# FPGA_IO.net
KiCad netlist of a schematic drawn in Altium Designer
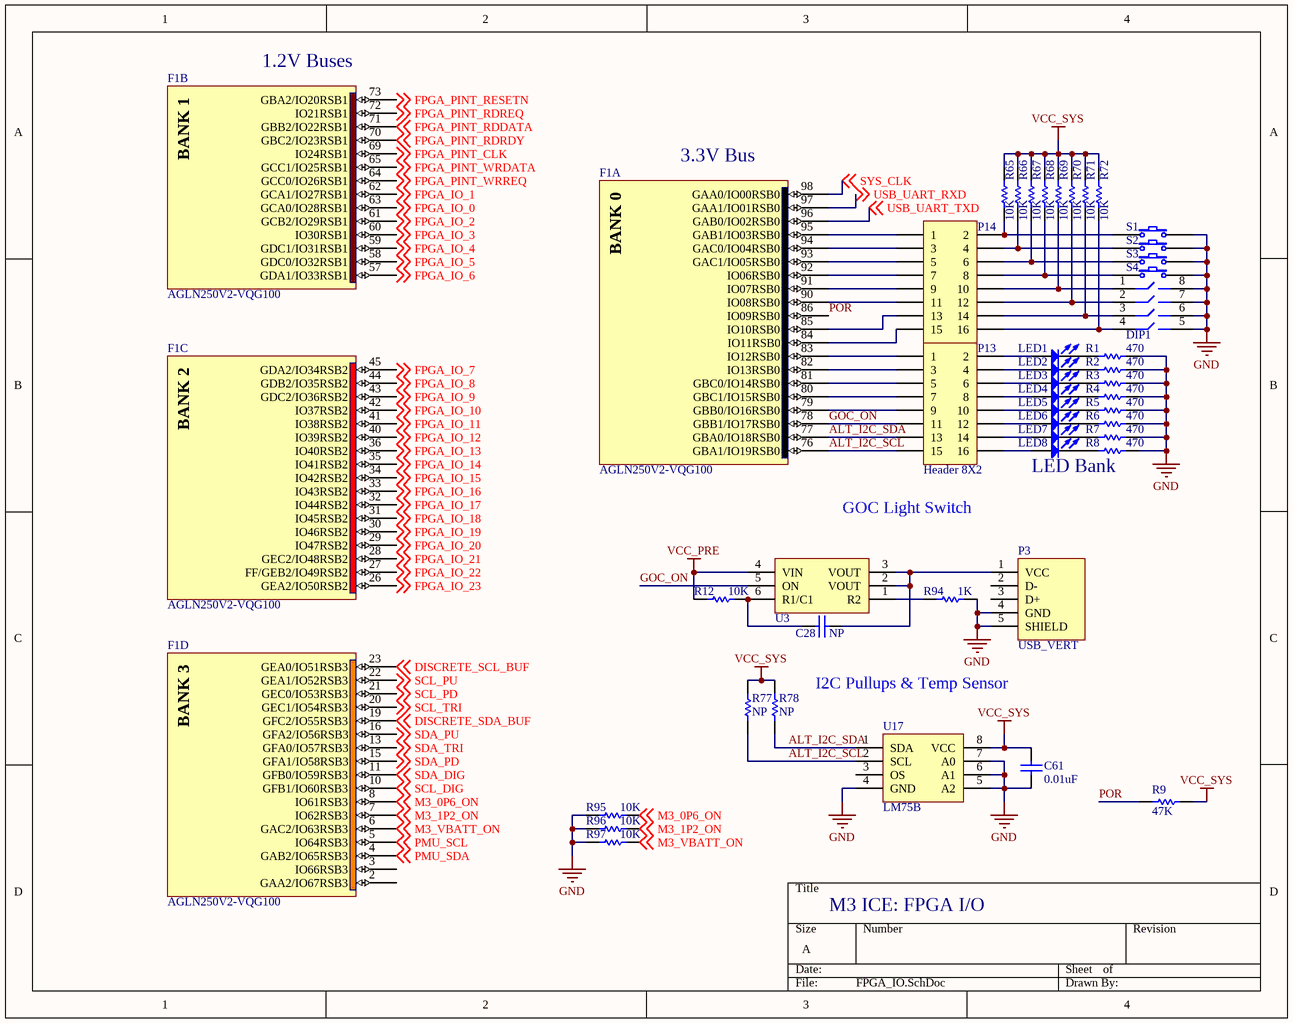
[diagram p0: FPGA_IO.SchDoc]

(export (version "E")
  (design (tool "Eeschema 10.0.6"))
  (components
    (comp (ref "C28")
      (value "NP")
      (footprint "0402")
      (description "Capacitor (Semiconductor SIM Model)")
      (fields (field (name "Comment") "Cap Semi") (field (name "PUBLISHER") "Altium Limited"))
      (libsource (lib "Miscellaneous Devices") (part "Cap Semi"))
    )
    (comp (ref "C61")
      (value "0.01uF")
      (footprint "1608[0603]")
      (description "Capacitor (Semiconductor SIM Model)")
      (fields
        (field (name "DISTPARTNO") "445-1311-1-ND")
        (field (name "MANPARTNO") "C1608X7R1H103K")
        (field (name "PUBLISHER") "Altium Limited")
      )
      (libsource (lib "Miscellaneous Devices") (part "Cap Semi"))
    )
    (comp (ref "DIP1")
      (value "ADE0404")
      (footprint "DIP-8")
      (description "4-DIP Switch")
      (fields (field (name "DISTPARTNO") "450-1364-ND"))
      (libsource (lib "M3") (part "ADE0404"))
    )
    (comp (ref "F1")
      (value "AGLN250V2-VQG100")
      (footprint "VQ100_N")
      (fields (field (name "DISTPARTNO") "1100-1134-ND") (field (name "PUBLISHER") "Altium Limited"))
      (libsource (lib "Actel IGLOO nano") (part "AGLN250V2-VQG100"))
    )
    (comp (ref "LED1")
      (value "LED 1206")
      (footprint "1206_LED")
      (fields (field (name "DISTPARTNO") "160-1169-1-ND") (field (name "MANPARTNO") "LTST-C150GKT"))
      (libsource (lib "M3") (part "LED 1206"))
    )
    (comp (ref "LED2")
      (value "LED 1206")
      (footprint "1206_LED")
      (fields (field (name "DISTPARTNO") "160-1169-1-ND") (field (name "MANPARTNO") "LTST-C150GKT"))
      (libsource (lib "M3") (part "LED 1206"))
    )
    (comp (ref "LED3")
      (value "LED 1206")
      (footprint "1206_LED")
      (fields (field (name "DISTPARTNO") "160-1169-1-ND") (field (name "MANPARTNO") "LTST-C150GKT"))
      (libsource (lib "M3") (part "LED 1206"))
    )
    (comp (ref "LED4")
      (value "LED 1206")
      (footprint "1206_LED")
      (fields (field (name "DISTPARTNO") "160-1169-1-ND") (field (name "MANPARTNO") "LTST-C150GKT"))
      (libsource (lib "M3") (part "LED 1206"))
    )
    (comp (ref "LED5")
      (value "LED 1206")
      (footprint "1206_LED")
      (fields (field (name "DISTPARTNO") "160-1169-1-ND") (field (name "MANPARTNO") "LTST-C150GKT"))
      (libsource (lib "M3") (part "LED 1206"))
    )
    (comp (ref "LED6")
      (value "LED 1206")
      (footprint "1206_LED")
      (fields (field (name "DISTPARTNO") "160-1169-1-ND") (field (name "MANPARTNO") "LTST-C150GKT"))
      (libsource (lib "M3") (part "LED 1206"))
    )
    (comp (ref "LED7")
      (value "LED 1206")
      (footprint "1206_LED")
      (fields (field (name "DISTPARTNO") "160-1169-1-ND") (field (name "MANPARTNO") "LTST-C150GKT"))
      (libsource (lib "M3") (part "LED 1206"))
    )
    (comp (ref "LED8")
      (value "LED 1206")
      (footprint "1206_LED")
      (fields (field (name "DISTPARTNO") "160-1169-1-ND") (field (name "MANPARTNO") "LTST-C150GKT"))
      (libsource (lib "M3") (part "LED 1206"))
    )
    (comp (ref "P3")
      (value "USB_VERT")
      (footprint "USB_VERT")
      (fields (field (name "DISTPARTNO") "ED2987-ND") (field (name "MANPARTNO") "USB-A1VSW6"))
      (libsource (lib "M3") (part "USB_VERT"))
    )
    (comp (ref "P13")
      (value "Header 8X2")
      (footprint "HDR2X8")
      (description "Header, 8-Pin, Dual row")
      (fields (field (name "PUBLISHER") "Altium Limited"))
      (libsource (lib "Miscellaneous Connectors") (part "Header 8X2"))
    )
    (comp (ref "P14")
      (value "Header 8X2")
      (footprint "HDR2X8")
      (description "Header, 8-Pin, Dual row")
      (fields (field (name "PUBLISHER") "Altium Limited"))
      (libsource (lib "Miscellaneous Connectors") (part "Header 8X2"))
    )
    (comp (ref "R1")
      (value "470")
      (footprint "0603")
      (description "Semiconductor Resistor")
      (fields
        (field (name "DISTPARTNO") "P470GCT-ND")
        (field (name "MANPARTNO") "ERJ-3GEYJ471V")
        (field (name "PUBLISHER") "Altium Limited")
      )
      (libsource (lib "M3") (part "Res Chip"))
    )
    (comp (ref "R2")
      (value "470")
      (footprint "0603")
      (description "Semiconductor Resistor")
      (fields
        (field (name "DISTPARTNO") "P470GCT-ND")
        (field (name "MANPARTNO") "ERJ-3GEYJ471V")
        (field (name "PUBLISHER") "Altium Limited")
      )
      (libsource (lib "M3") (part "Res Chip"))
    )
    (comp (ref "R3")
      (value "470")
      (footprint "0603")
      (description "Semiconductor Resistor")
      (fields
        (field (name "DISTPARTNO") "P470GCT-ND")
        (field (name "MANPARTNO") "ERJ-3GEYJ471V")
        (field (name "PUBLISHER") "Altium Limited")
      )
      (libsource (lib "M3") (part "Res Chip"))
    )
    (comp (ref "R4")
      (value "470")
      (footprint "0603")
      (description "Semiconductor Resistor")
      (fields
        (field (name "DISTPARTNO") "P470GCT-ND")
        (field (name "MANPARTNO") "ERJ-3GEYJ471V")
        (field (name "PUBLISHER") "Altium Limited")
      )
      (libsource (lib "M3") (part "Res Chip"))
    )
    (comp (ref "R5")
      (value "470")
      (footprint "0603")
      (description "Semiconductor Resistor")
      (fields
        (field (name "DISTPARTNO") "P470GCT-ND")
        (field (name "MANPARTNO") "ERJ-3GEYJ471V")
        (field (name "PUBLISHER") "Altium Limited")
      )
      (libsource (lib "M3") (part "Res Chip"))
    )
    (comp (ref "R6")
      (value "470")
      (footprint "0603")
      (description "Semiconductor Resistor")
      (fields
        (field (name "DISTPARTNO") "P470GCT-ND")
        (field (name "MANPARTNO") "ERJ-3GEYJ471V")
        (field (name "PUBLISHER") "Altium Limited")
      )
      (libsource (lib "M3") (part "Res Chip"))
    )
    (comp (ref "R7")
      (value "470")
      (footprint "0603")
      (description "Semiconductor Resistor")
      (fields
        (field (name "DISTPARTNO") "P470GCT-ND")
        (field (name "MANPARTNO") "ERJ-3GEYJ471V")
        (field (name "PUBLISHER") "Altium Limited")
      )
      (libsource (lib "M3") (part "Res Chip"))
    )
    (comp (ref "R8")
      (value "470")
      (footprint "0603")
      (description "Semiconductor Resistor")
      (fields
        (field (name "DISTPARTNO") "P470GCT-ND")
        (field (name "MANPARTNO") "ERJ-3GEYJ471V")
        (field (name "PUBLISHER") "Altium Limited")
      )
      (libsource (lib "M3") (part "Res Chip"))
    )
    (comp (ref "R9")
      (value "47K")
      (footprint "0603")
      (description "Semiconductor Resistor")
      (fields
        (field (name "DISTPARTNO") "P47KGCT-ND")
        (field (name "MANPARTNO") "ERJ-3GEYJ103V")
        (field (name "PUBLISHER") "Altium Limited")
      )
      (libsource (lib "M3") (part "Res Chip"))
    )
    (comp (ref "R12")
      (value "10K")
      (footprint "0402")
      (description "Semiconductor Resistor")
      (fields
        (field (name "MANPARTNO") "ERJ-2RKF1002X")
        (field (name "DISTPARTNO") "P10.0KLCT-ND")
        (field (name "PUBLISHER") "Altium Limited")
      )
      (libsource (lib "M3") (part "Res Chip"))
    )
    (comp (ref "R65")
      (value "10K")
      (footprint "0603")
      (description "Semiconductor Resistor")
      (fields
        (field (name "DISTPARTNO") "P10KGCT-ND")
        (field (name "MANPARTNO") "ERJ-3GEYJ103V")
        (field (name "PUBLISHER") "Altium Limited")
      )
      (libsource (lib "M3") (part "Res Chip"))
    )
    (comp (ref "R66")
      (value "10K")
      (footprint "0603")
      (description "Semiconductor Resistor")
      (fields
        (field (name "DISTPARTNO") "P10KGCT-ND")
        (field (name "MANPARTNO") "ERJ-3GEYJ103V")
        (field (name "PUBLISHER") "Altium Limited")
      )
      (libsource (lib "M3") (part "Res Chip"))
    )
    (comp (ref "R67")
      (value "10K")
      (footprint "0603")
      (description "Semiconductor Resistor")
      (fields
        (field (name "DISTPARTNO") "P10KGCT-ND")
        (field (name "MANPARTNO") "ERJ-3GEYJ103V")
        (field (name "PUBLISHER") "Altium Limited")
      )
      (libsource (lib "M3") (part "Res Chip"))
    )
    (comp (ref "R68")
      (value "10K")
      (footprint "0603")
      (description "Semiconductor Resistor")
      (fields
        (field (name "DISTPARTNO") "P10KGCT-ND")
        (field (name "MANPARTNO") "ERJ-3GEYJ103V")
        (field (name "PUBLISHER") "Altium Limited")
      )
      (libsource (lib "M3") (part "Res Chip"))
    )
    (comp (ref "R69")
      (value "10K")
      (footprint "0603")
      (description "Semiconductor Resistor")
      (fields
        (field (name "DISTPARTNO") "P10KGCT-ND")
        (field (name "MANPARTNO") "ERJ-3GEYJ103V")
        (field (name "PUBLISHER") "Altium Limited")
      )
      (libsource (lib "M3") (part "Res Chip"))
    )
    (comp (ref "R70")
      (value "10K")
      (footprint "0603")
      (description "Semiconductor Resistor")
      (fields
        (field (name "DISTPARTNO") "P10KGCT-ND")
        (field (name "MANPARTNO") "ERJ-3GEYJ103V")
        (field (name "PUBLISHER") "Altium Limited")
      )
      (libsource (lib "M3") (part "Res Chip"))
    )
    (comp (ref "R71")
      (value "10K")
      (footprint "0603")
      (description "Semiconductor Resistor")
      (fields
        (field (name "DISTPARTNO") "P10KGCT-ND")
        (field (name "MANPARTNO") "ERJ-3GEYJ103V")
        (field (name "PUBLISHER") "Altium Limited")
      )
      (libsource (lib "M3") (part "Res Chip"))
    )
    (comp (ref "R72")
      (value "10K")
      (footprint "0603")
      (description "Semiconductor Resistor")
      (fields
        (field (name "DISTPARTNO") "P10KGCT-ND")
        (field (name "MANPARTNO") "ERJ-3GEYJ103V")
        (field (name "PUBLISHER") "Altium Limited")
      )
      (libsource (lib "M3") (part "Res Chip"))
    )
    (comp (ref "R77")
      (value "NP")
      (footprint "0603")
      (description "Semiconductor Resistor")
      (fields
        (field (name "DISTPARTNO") "NONE")
        (field (name "Comment") "Res Chip")
        (field (name "PUBLISHER") "Altium Limited")
      )
      (libsource (lib "M3") (part "Res Chip"))
    )
    (comp (ref "R78")
      (value "NP")
      (footprint "0603")
      (description "Semiconductor Resistor")
      (fields
        (field (name "DISTPARTNO") "NONE")
        (field (name "Comment") "Res Chip")
        (field (name "PUBLISHER") "Altium Limited")
      )
      (libsource (lib "M3") (part "Res Chip"))
    )
    (comp (ref "R94")
      (value "1K")
      (footprint "0402")
      (description "Semiconductor Resistor")
      (fields
        (field (name "MANPARTNO") "ERJ-2RKF1001X")
        (field (name "DISTPARTNO") "P1.00KLCT-ND")
        (field (name "PUBLISHER") "Altium Limited")
      )
      (libsource (lib "M3") (part "Res Chip"))
    )
    (comp (ref "R95")
      (value "10K")
      (footprint "0402")
      (description "Semiconductor Resistor")
      (fields
        (field (name "DISTPARTNO") "P10.0KLCT-ND")
        (field (name "MANPARTNO") "ERJ-2RKF1002X")
        (field (name "PUBLISHER") "Altium Limited")
      )
      (libsource (lib "M3") (part "Res Chip"))
    )
    (comp (ref "R96")
      (value "10K")
      (footprint "0402")
      (description "Semiconductor Resistor")
      (fields
        (field (name "DISTPARTNO") "P10.0KLCT-ND")
        (field (name "MANPARTNO") "ERJ-2RKF1002X")
        (field (name "PUBLISHER") "Altium Limited")
      )
      (libsource (lib "M3") (part "Res Chip"))
    )
    (comp (ref "R97")
      (value "10K")
      (footprint "0402")
      (description "Semiconductor Resistor")
      (fields
        (field (name "DISTPARTNO") "P10.0KLCT-ND")
        (field (name "MANPARTNO") "ERJ-2RKF1002X")
        (field (name "PUBLISHER") "Altium Limited")
      )
      (libsource (lib "M3") (part "Res Chip"))
    )
    (comp (ref "S1")
      (value "EVQ-PAE04M")
      (footprint "EVQPA")
      (description "Switch Push")
      (fields (field (name "DISTPARTNO") "P8008S-ND"))
      (libsource (lib "M3") (part "EVQ-PAE04M"))
    )
    (comp (ref "S2")
      (value "EVQ-PAE04M")
      (footprint "EVQPA")
      (description "Switch Push")
      (fields (field (name "DISTPARTNO") "P8008S-ND"))
      (libsource (lib "M3") (part "EVQ-PAE04M"))
    )
    (comp (ref "S3")
      (value "EVQ-PAE04M")
      (footprint "EVQPA")
      (description "Switch Push")
      (fields (field (name "DISTPARTNO") "P8008S-ND"))
      (libsource (lib "M3") (part "EVQ-PAE04M"))
    )
    (comp (ref "S4")
      (value "EVQ-PAE04M")
      (footprint "EVQPA")
      (description "Switch Push")
      (fields (field (name "DISTPARTNO") "P8008S-ND"))
      (libsource (lib "M3") (part "EVQ-PAE04M"))
    )
    (comp (ref "U3")
      (value "FDC6330L")
      (footprint "SUPERSOT-6")
      (description "HS Switch")
      (fields (field (name "DISTPARTNO") "FDC6330LCT-ND"))
      (libsource (lib "M3") (part "FDC6330L"))
    )
    (comp (ref "U17")
      (value "LM75B")
      (footprint "SO8")
      (description "I2C Temp Sensor")
      (fields (field (name "DISTPARTNO") "568-4688-1-ND") (field (name "MANPARTNO") "LM75BD,118"))
      (libsource (lib "M3") (part "LM75B"))
    )
  )
  (nets
    (net (code "1") (name "/ALT_I2C_SCL") (class "Default")
      (node (ref "F1") (pin "76") (pinfunction "GBA1/IO19RSB0_76") (pintype "bidirectional"))
      (node (ref "P13") (pin "15") (pinfunction "15_15") (pintype "passive"))
      (node (ref "R77") (pin "2") (pinfunction "2_2") (pintype "passive"))
      (node (ref "U17") (pin "2") (pinfunction "SCL_2") (pintype "passive"))
    )
    (net (code "2") (name "/ALT_I2C_SDA") (class "Default")
      (node (ref "F1") (pin "77") (pinfunction "GBA0/IO18RSB0_77") (pintype "bidirectional"))
      (node (ref "P13") (pin "13") (pinfunction "13_13") (pintype "passive"))
      (node (ref "R78") (pin "2") (pinfunction "2_2") (pintype "passive"))
      (node (ref "U17") (pin "1") (pinfunction "SDA_1") (pintype "passive"))
    )
    (net (code "3") (name "/GOC_ON") (class "Default")
      (node (ref "F1") (pin "78") (pinfunction "GBB1/IO17RSB0_78") (pintype "bidirectional"))
      (node (ref "P13") (pin "11") (pinfunction "11_11") (pintype "passive"))
      (node (ref "U3") (pin "5") (pinfunction "ON_5") (pintype "passive"))
    )
    (net (code "4") (name "/POR") (class "Default")
      (node (ref "F1") (pin "86") (pinfunction "IO09RSB0_86") (pintype "bidirectional"))
      (node (ref "R9") (pin "1") (pinfunction "1_1") (pintype "passive"))
    )
    (net (code "5") (name "DISCRETE_SCL_BUF") (class "Default")
      (node (ref "F1") (pin "23") (pinfunction "GEA0/IO51RSB3_23") (pintype "bidirectional"))
    )
    (net (code "6") (name "DISCRETE_SDA_BUF") (class "Default")
      (node (ref "F1") (pin "19") (pinfunction "GFC2/IO55RSB3_19") (pintype "bidirectional"))
    )
    (net (code "7") (name "FPGA_IO_0") (class "Default")
      (node (ref "F1") (pin "63") (pinfunction "GCA0/IO28RSB1_63") (pintype "bidirectional"))
    )
    (net (code "8") (name "FPGA_IO_1") (class "Default")
      (node (ref "F1") (pin "62") (pinfunction "GCA1/IO27RSB1_62") (pintype "bidirectional"))
    )
    (net (code "9") (name "FPGA_IO_2") (class "Default")
      (node (ref "F1") (pin "61") (pinfunction "GCB2/IO29RSB1_61") (pintype "bidirectional"))
    )
    (net (code "10") (name "FPGA_IO_3") (class "Default")
      (node (ref "F1") (pin "60") (pinfunction "IO30RSB1_60") (pintype "bidirectional"))
    )
    (net (code "11") (name "FPGA_IO_4") (class "Default")
      (node (ref "F1") (pin "59") (pinfunction "GDC1/IO31RSB1_59") (pintype "bidirectional"))
    )
    (net (code "12") (name "FPGA_IO_5") (class "Default")
      (node (ref "F1") (pin "58") (pinfunction "GDC0/IO32RSB1_58") (pintype "bidirectional"))
    )
    (net (code "13") (name "FPGA_IO_6") (class "Default")
      (node (ref "F1") (pin "57") (pinfunction "GDA1/IO33RSB1_57") (pintype "bidirectional"))
    )
    (net (code "14") (name "FPGA_IO_7") (class "Default")
      (node (ref "F1") (pin "45") (pinfunction "GDA2/IO34RSB2_45") (pintype "bidirectional"))
    )
    (net (code "15") (name "FPGA_IO_8") (class "Default")
      (node (ref "F1") (pin "44") (pinfunction "GDB2/IO35RSB2_44") (pintype "bidirectional"))
    )
    (net (code "16") (name "FPGA_IO_9") (class "Default")
      (node (ref "F1") (pin "43") (pinfunction "GDC2/IO36RSB2_43") (pintype "bidirectional"))
    )
    (net (code "17") (name "FPGA_IO_10") (class "Default")
      (node (ref "F1") (pin "42") (pinfunction "IO37RSB2_42") (pintype "bidirectional"))
    )
    (net (code "18") (name "FPGA_IO_11") (class "Default")
      (node (ref "F1") (pin "41") (pinfunction "IO38RSB2_41") (pintype "bidirectional"))
    )
    (net (code "19") (name "FPGA_IO_12") (class "Default")
      (node (ref "F1") (pin "40") (pinfunction "IO39RSB2_40") (pintype "bidirectional"))
    )
    (net (code "20") (name "FPGA_IO_13") (class "Default")
      (node (ref "F1") (pin "36") (pinfunction "IO40RSB2_36") (pintype "bidirectional"))
    )
    (net (code "21") (name "FPGA_IO_14") (class "Default")
      (node (ref "F1") (pin "35") (pinfunction "IO41RSB2_35") (pintype "bidirectional"))
    )
    (net (code "22") (name "FPGA_IO_15") (class "Default")
      (node (ref "F1") (pin "34") (pinfunction "IO42RSB2_34") (pintype "bidirectional"))
    )
    (net (code "23") (name "FPGA_IO_16") (class "Default")
      (node (ref "F1") (pin "33") (pinfunction "IO43RSB2_33") (pintype "bidirectional"))
    )
    (net (code "24") (name "FPGA_IO_17") (class "Default")
      (node (ref "F1") (pin "32") (pinfunction "IO44RSB2_32") (pintype "bidirectional"))
    )
    (net (code "25") (name "FPGA_IO_18") (class "Default")
      (node (ref "F1") (pin "31") (pinfunction "IO45RSB2_31") (pintype "bidirectional"))
    )
    (net (code "26") (name "FPGA_IO_19") (class "Default")
      (node (ref "F1") (pin "30") (pinfunction "IO46RSB2_30") (pintype "bidirectional"))
    )
    (net (code "27") (name "FPGA_IO_20") (class "Default")
      (node (ref "F1") (pin "29") (pinfunction "IO47RSB2_29") (pintype "bidirectional"))
    )
    (net (code "28") (name "FPGA_IO_21") (class "Default")
      (node (ref "F1") (pin "28") (pinfunction "GEC2/IO48RSB2_28") (pintype "bidirectional"))
    )
    (net (code "29") (name "FPGA_IO_22") (class "Default")
      (node (ref "F1") (pin "27") (pinfunction "FF/GEB2/IO49RSB2_27") (pintype "bidirectional"))
    )
    (net (code "30") (name "FPGA_IO_23") (class "Default")
      (node (ref "F1") (pin "26") (pinfunction "GEA2/IO50RSB2_26") (pintype "bidirectional"))
    )
    (net (code "31") (name "FPGA_PINT_CLK") (class "Default")
      (node (ref "F1") (pin "69") (pinfunction "IO24RSB1_69") (pintype "bidirectional"))
    )
    (net (code "32") (name "FPGA_PINT_RDDATA") (class "Default")
      (node (ref "F1") (pin "71") (pinfunction "GBB2/IO22RSB1_71") (pintype "bidirectional"))
    )
    (net (code "33") (name "FPGA_PINT_RDRDY") (class "Default")
      (node (ref "F1") (pin "70") (pinfunction "GBC2/IO23RSB1_70") (pintype "bidirectional"))
    )
    (net (code "34") (name "FPGA_PINT_RDREQ") (class "Default")
      (node (ref "F1") (pin "72") (pinfunction "IO21RSB1_72") (pintype "bidirectional"))
    )
    (net (code "35") (name "FPGA_PINT_RESETN") (class "Default")
      (node (ref "F1") (pin "73") (pinfunction "GBA2/IO20RSB1_73") (pintype "bidirectional"))
    )
    (net (code "36") (name "FPGA_PINT_WRDATA") (class "Default")
      (node (ref "F1") (pin "65") (pinfunction "GCC1/IO25RSB1_65") (pintype "bidirectional"))
    )
    (net (code "37") (name "FPGA_PINT_WRREQ") (class "Default")
      (node (ref "F1") (pin "64") (pinfunction "GCC0/IO26RSB1_64") (pintype "bidirectional"))
    )
    (net (code "38") (name "GND") (class "Default")
      (node (ref "C61") (pin "1") (pinfunction "1_1") (pintype "passive"))
      (node (ref "DIP1") (pin "5") (pinfunction "5_5") (pintype "passive"))
      (node (ref "DIP1") (pin "6") (pinfunction "6_6") (pintype "passive"))
      (node (ref "DIP1") (pin "7") (pinfunction "7_7") (pintype "passive"))
      (node (ref "DIP1") (pin "8") (pinfunction "8_8") (pintype "passive"))
      (node (ref "P3") (pin "4") (pinfunction "GND_4") (pintype "passive"))
      (node (ref "P3") (pin "5") (pinfunction "SHIELD_5") (pintype "passive"))
      (node (ref "R1") (pin "1") (pinfunction "1_1") (pintype "passive"))
      (node (ref "R2") (pin "1") (pinfunction "1_1") (pintype "passive"))
      (node (ref "R3") (pin "1") (pinfunction "1_1") (pintype "passive"))
      (node (ref "R4") (pin "1") (pinfunction "1_1") (pintype "passive"))
      (node (ref "R5") (pin "1") (pinfunction "1_1") (pintype "passive"))
      (node (ref "R6") (pin "1") (pinfunction "1_1") (pintype "passive"))
      (node (ref "R7") (pin "1") (pinfunction "1_1") (pintype "passive"))
      (node (ref "R8") (pin "1") (pinfunction "1_1") (pintype "passive"))
      (node (ref "R94") (pin "2") (pinfunction "2_2") (pintype "passive"))
      (node (ref "R95") (pin "2") (pinfunction "2_2") (pintype "passive"))
      (node (ref "R96") (pin "2") (pinfunction "2_2") (pintype "passive"))
      (node (ref "R97") (pin "2") (pinfunction "2_2") (pintype "passive"))
      (node (ref "S1") (pin "2") (pinfunction "2_2") (pintype "passive"))
      (node (ref "S2") (pin "2") (pinfunction "2_2") (pintype "passive"))
      (node (ref "S3") (pin "2") (pinfunction "2_2") (pintype "passive"))
      (node (ref "S4") (pin "2") (pinfunction "2_2") (pintype "passive"))
      (node (ref "U17") (pin "4") (pinfunction "GND_4") (pintype "passive"))
      (node (ref "U17") (pin "5") (pinfunction "A2_5") (pintype "passive"))
      (node (ref "U17") (pin "6") (pinfunction "A1_6") (pintype "passive"))
      (node (ref "U17") (pin "7") (pinfunction "A0_7") (pintype "passive"))
    )
    (net (code "39") (name "M3_0P6_ON") (class "Default")
      (node (ref "F1") (pin "8") (pinfunction "IO61RSB3_8") (pintype "bidirectional"))
      (node (ref "R95") (pin "1") (pinfunction "1_1") (pintype "passive"))
    )
    (net (code "40") (name "M3_1P2_ON") (class "Default")
      (node (ref "F1") (pin "7") (pinfunction "IO62RSB3_7") (pintype "bidirectional"))
      (node (ref "R96") (pin "1") (pinfunction "1_1") (pintype "passive"))
    )
    (net (code "41") (name "M3_VBATT_ON") (class "Default")
      (node (ref "F1") (pin "6") (pinfunction "GAC2/IO63RSB3_6") (pintype "bidirectional"))
      (node (ref "R97") (pin "1") (pinfunction "1_1") (pintype "passive"))
    )
    (net (code "42") (name "Net-(DIP1-Pad1)") (class "Default")
      (node (ref "DIP1") (pin "1") (pinfunction "1_1") (pintype "passive"))
      (node (ref "P14") (pin "10") (pinfunction "10_10") (pintype "passive"))
      (node (ref "R69") (pin "2") (pinfunction "2_2") (pintype "passive"))
    )
    (net (code "43") (name "Net-(DIP1-Pad2)") (class "Default")
      (node (ref "DIP1") (pin "2") (pinfunction "2_2") (pintype "passive"))
      (node (ref "P14") (pin "12") (pinfunction "12_12") (pintype "passive"))
      (node (ref "R70") (pin "2") (pinfunction "2_2") (pintype "passive"))
    )
    (net (code "44") (name "Net-(DIP1-Pad3)") (class "Default")
      (node (ref "DIP1") (pin "3") (pinfunction "3_3") (pintype "passive"))
      (node (ref "P14") (pin "14") (pinfunction "14_14") (pintype "passive"))
      (node (ref "R71") (pin "2") (pinfunction "2_2") (pintype "passive"))
    )
    (net (code "45") (name "Net-(DIP1-Pad4)") (class "Default")
      (node (ref "DIP1") (pin "4") (pinfunction "4_4") (pintype "passive"))
      (node (ref "P14") (pin "16") (pinfunction "16_16") (pintype "passive"))
      (node (ref "R72") (pin "2") (pinfunction "2_2") (pintype "passive"))
    )
    (net (code "46") (name "Net-(F1A-GAB1{slash}IO03RSB0)") (class "Default")
      (node (ref "F1") (pin "95") (pinfunction "GAB1/IO03RSB0_95") (pintype "bidirectional"))
      (node (ref "P14") (pin "1") (pinfunction "1_1") (pintype "passive"))
    )
    (net (code "47") (name "Net-(F1A-GAC0{slash}IO04RSB0)") (class "Default")
      (node (ref "F1") (pin "94") (pinfunction "GAC0/IO04RSB0_94") (pintype "bidirectional"))
      (node (ref "P14") (pin "3") (pinfunction "3_3") (pintype "passive"))
    )
    (net (code "48") (name "Net-(F1A-GAC1{slash}IO05RSB0)") (class "Default")
      (node (ref "F1") (pin "93") (pinfunction "GAC1/IO05RSB0_93") (pintype "bidirectional"))
      (node (ref "P14") (pin "5") (pinfunction "5_5") (pintype "passive"))
    )
    (net (code "49") (name "Net-(F1A-GBB0{slash}IO16RSB0)") (class "Default")
      (node (ref "F1") (pin "79") (pinfunction "GBB0/IO16RSB0_79") (pintype "bidirectional"))
      (node (ref "P13") (pin "9") (pinfunction "9_9") (pintype "passive"))
    )
    (net (code "50") (name "Net-(F1A-GBC0{slash}IO14RSB0)") (class "Default")
      (node (ref "F1") (pin "81") (pinfunction "GBC0/IO14RSB0_81") (pintype "bidirectional"))
      (node (ref "P13") (pin "5") (pinfunction "5_5") (pintype "passive"))
    )
    (net (code "51") (name "Net-(F1A-GBC1{slash}IO15RSB0)") (class "Default")
      (node (ref "F1") (pin "80") (pinfunction "GBC1/IO15RSB0_80") (pintype "bidirectional"))
      (node (ref "P13") (pin "7") (pinfunction "7_7") (pintype "passive"))
    )
    (net (code "52") (name "Net-(F1A-IO06RSB0)") (class "Default")
      (node (ref "F1") (pin "92") (pinfunction "IO06RSB0_92") (pintype "bidirectional"))
      (node (ref "P14") (pin "7") (pinfunction "7_7") (pintype "passive"))
    )
    (net (code "53") (name "Net-(F1A-IO07RSB0)") (class "Default")
      (node (ref "F1") (pin "91") (pinfunction "IO07RSB0_91") (pintype "bidirectional"))
      (node (ref "P14") (pin "9") (pinfunction "9_9") (pintype "passive"))
    )
    (net (code "54") (name "Net-(F1A-IO08RSB0)") (class "Default")
      (node (ref "F1") (pin "90") (pinfunction "IO08RSB0_90") (pintype "bidirectional"))
      (node (ref "P14") (pin "11") (pinfunction "11_11") (pintype "passive"))
    )
    (net (code "55") (name "Net-(F1A-IO10RSB0)") (class "Default")
      (node (ref "F1") (pin "85") (pinfunction "IO10RSB0_85") (pintype "bidirectional"))
      (node (ref "P14") (pin "13") (pinfunction "13_13") (pintype "passive"))
    )
    (net (code "56") (name "Net-(F1A-IO11RSB0)") (class "Default")
      (node (ref "F1") (pin "84") (pinfunction "IO11RSB0_84") (pintype "bidirectional"))
      (node (ref "P14") (pin "15") (pinfunction "15_15") (pintype "passive"))
    )
    (net (code "57") (name "Net-(F1A-IO12RSB0)") (class "Default")
      (node (ref "F1") (pin "83") (pinfunction "IO12RSB0_83") (pintype "bidirectional"))
      (node (ref "P13") (pin "1") (pinfunction "1_1") (pintype "passive"))
    )
    (net (code "58") (name "Net-(F1A-IO13RSB0)") (class "Default")
      (node (ref "F1") (pin "82") (pinfunction "IO13RSB0_82") (pintype "bidirectional"))
      (node (ref "P13") (pin "3") (pinfunction "3_3") (pintype "passive"))
    )
    (net (code "59") (name "Net-(LED1-A)") (class "Default")
      (node (ref "LED1") (pin "1") (pinfunction "A_1") (pintype "passive"))
      (node (ref "P13") (pin "2") (pinfunction "2_2") (pintype "passive"))
    )
    (net (code "60") (name "Net-(LED1-K)") (class "Default")
      (node (ref "LED1") (pin "2") (pinfunction "K_2") (pintype "passive"))
      (node (ref "R1") (pin "2") (pinfunction "2_2") (pintype "passive"))
    )
    (net (code "61") (name "Net-(LED2-A)") (class "Default")
      (node (ref "LED2") (pin "1") (pinfunction "A_1") (pintype "passive"))
      (node (ref "P13") (pin "4") (pinfunction "4_4") (pintype "passive"))
    )
    (net (code "62") (name "Net-(LED2-K)") (class "Default")
      (node (ref "LED2") (pin "2") (pinfunction "K_2") (pintype "passive"))
      (node (ref "R2") (pin "2") (pinfunction "2_2") (pintype "passive"))
    )
    (net (code "63") (name "Net-(LED3-A)") (class "Default")
      (node (ref "LED3") (pin "1") (pinfunction "A_1") (pintype "passive"))
      (node (ref "P13") (pin "6") (pinfunction "6_6") (pintype "passive"))
    )
    (net (code "64") (name "Net-(LED3-K)") (class "Default")
      (node (ref "LED3") (pin "2") (pinfunction "K_2") (pintype "passive"))
      (node (ref "R3") (pin "2") (pinfunction "2_2") (pintype "passive"))
    )
    (net (code "65") (name "Net-(LED4-A)") (class "Default")
      (node (ref "LED4") (pin "1") (pinfunction "A_1") (pintype "passive"))
      (node (ref "P13") (pin "8") (pinfunction "8_8") (pintype "passive"))
    )
    (net (code "66") (name "Net-(LED4-K)") (class "Default")
      (node (ref "LED4") (pin "2") (pinfunction "K_2") (pintype "passive"))
      (node (ref "R4") (pin "2") (pinfunction "2_2") (pintype "passive"))
    )
    (net (code "67") (name "Net-(LED5-A)") (class "Default")
      (node (ref "LED5") (pin "1") (pinfunction "A_1") (pintype "passive"))
      (node (ref "P13") (pin "10") (pinfunction "10_10") (pintype "passive"))
    )
    (net (code "68") (name "Net-(LED5-K)") (class "Default")
      (node (ref "LED5") (pin "2") (pinfunction "K_2") (pintype "passive"))
      (node (ref "R5") (pin "2") (pinfunction "2_2") (pintype "passive"))
    )
    (net (code "69") (name "Net-(LED6-A)") (class "Default")
      (node (ref "LED6") (pin "1") (pinfunction "A_1") (pintype "passive"))
      (node (ref "P13") (pin "12") (pinfunction "12_12") (pintype "passive"))
    )
    (net (code "70") (name "Net-(LED6-K)") (class "Default")
      (node (ref "LED6") (pin "2") (pinfunction "K_2") (pintype "passive"))
      (node (ref "R6") (pin "2") (pinfunction "2_2") (pintype "passive"))
    )
    (net (code "71") (name "Net-(LED7-A)") (class "Default")
      (node (ref "LED7") (pin "1") (pinfunction "A_1") (pintype "passive"))
      (node (ref "P13") (pin "14") (pinfunction "14_14") (pintype "passive"))
    )
    (net (code "72") (name "Net-(LED7-K)") (class "Default")
      (node (ref "LED7") (pin "2") (pinfunction "K_2") (pintype "passive"))
      (node (ref "R7") (pin "2") (pinfunction "2_2") (pintype "passive"))
    )
    (net (code "73") (name "Net-(LED8-A)") (class "Default")
      (node (ref "LED8") (pin "1") (pinfunction "A_1") (pintype "passive"))
      (node (ref "P13") (pin "16") (pinfunction "16_16") (pintype "passive"))
    )
    (net (code "74") (name "Net-(LED8-K)") (class "Default")
      (node (ref "LED8") (pin "2") (pinfunction "K_2") (pintype "passive"))
      (node (ref "R8") (pin "2") (pinfunction "2_2") (pintype "passive"))
    )
    (net (code "75") (name "Net-(P3-VCC)") (class "Default")
      (node (ref "C28") (pin "1") (pinfunction "1_1") (pintype "passive"))
      (node (ref "P3") (pin "1") (pinfunction "VCC_1") (pintype "passive"))
      (node (ref "U3") (pin "2") (pinfunction "VOUT_2") (pintype "passive"))
      (node (ref "U3") (pin "3") (pinfunction "VOUT_3") (pintype "passive"))
    )
    (net (code "76") (name "Net-(P14-Pad2)") (class "Default")
      (node (ref "P14") (pin "2") (pinfunction "2_2") (pintype "passive"))
      (node (ref "R65") (pin "2") (pinfunction "2_2") (pintype "passive"))
      (node (ref "S1") (pin "1") (pinfunction "1_1") (pintype "passive"))
    )
    (net (code "77") (name "Net-(P14-Pad4)") (class "Default")
      (node (ref "P14") (pin "4") (pinfunction "4_4") (pintype "passive"))
      (node (ref "R66") (pin "2") (pinfunction "2_2") (pintype "passive"))
      (node (ref "S2") (pin "1") (pinfunction "1_1") (pintype "passive"))
    )
    (net (code "78") (name "Net-(P14-Pad6)") (class "Default")
      (node (ref "P14") (pin "6") (pinfunction "6_6") (pintype "passive"))
      (node (ref "R67") (pin "2") (pinfunction "2_2") (pintype "passive"))
      (node (ref "S3") (pin "1") (pinfunction "1_1") (pintype "passive"))
    )
    (net (code "79") (name "Net-(P14-Pad8)") (class "Default")
      (node (ref "P14") (pin "8") (pinfunction "8_8") (pintype "passive"))
      (node (ref "R68") (pin "2") (pinfunction "2_2") (pintype "passive"))
      (node (ref "S4") (pin "1") (pinfunction "1_1") (pintype "passive"))
    )
    (net (code "80") (name "Net-(U3-R1{slash}C1)") (class "Default")
      (node (ref "C28") (pin "2") (pinfunction "2_2") (pintype "passive"))
      (node (ref "R12") (pin "2") (pinfunction "2_2") (pintype "passive"))
      (node (ref "U3") (pin "6") (pinfunction "R1/C1_6") (pintype "passive"))
    )
    (net (code "81") (name "Net-(U3-R2)") (class "Default")
      (node (ref "R94") (pin "1") (pinfunction "1_1") (pintype "passive"))
      (node (ref "U3") (pin "1") (pinfunction "R2_1") (pintype "passive"))
    )
    (net (code "82") (name "PMU_SCL") (class "Default")
      (node (ref "F1") (pin "5") (pinfunction "IO64RSB3_5") (pintype "bidirectional"))
    )
    (net (code "83") (name "PMU_SDA") (class "Default")
      (node (ref "F1") (pin "4") (pinfunction "GAB2/IO65RSB3_4") (pintype "bidirectional"))
    )
    (net (code "84") (name "SCL_DIG") (class "Default")
      (node (ref "F1") (pin "10") (pinfunction "GFB1/IO60RSB3_10") (pintype "bidirectional"))
    )
    (net (code "85") (name "SCL_PD") (class "Default")
      (node (ref "F1") (pin "21") (pinfunction "GEC0/IO53RSB3_21") (pintype "bidirectional"))
    )
    (net (code "86") (name "SCL_PU") (class "Default")
      (node (ref "F1") (pin "22") (pinfunction "GEA1/IO52RSB3_22") (pintype "bidirectional"))
    )
    (net (code "87") (name "SCL_TRI") (class "Default")
      (node (ref "F1") (pin "20") (pinfunction "GEC1/IO54RSB3_20") (pintype "bidirectional"))
    )
    (net (code "88") (name "SDA_DIG") (class "Default")
      (node (ref "F1") (pin "11") (pinfunction "GFB0/IO59RSB3_11") (pintype "bidirectional"))
    )
    (net (code "89") (name "SDA_PD") (class "Default")
      (node (ref "F1") (pin "15") (pinfunction "GFA1/IO58RSB3_15") (pintype "bidirectional"))
    )
    (net (code "90") (name "SDA_PU") (class "Default")
      (node (ref "F1") (pin "16") (pinfunction "GFA2/IO56RSB3_16") (pintype "bidirectional"))
    )
    (net (code "91") (name "SDA_TRI") (class "Default")
      (node (ref "F1") (pin "13") (pinfunction "GFA0/IO57RSB3_13") (pintype "bidirectional"))
    )
    (net (code "92") (name "SYS_CLK") (class "Default")
      (node (ref "F1") (pin "98") (pinfunction "GAA0/IO00RSB0_98") (pintype "bidirectional"))
    )
    (net (code "93") (name "USB_UART_RXD") (class "Default")
      (node (ref "F1") (pin "97") (pinfunction "GAA1/IO01RSB0_97") (pintype "bidirectional"))
    )
    (net (code "94") (name "USB_UART_TXD") (class "Default")
      (node (ref "F1") (pin "96") (pinfunction "GAB0/IO02RSB0_96") (pintype "bidirectional"))
    )
    (net (code "95") (name "VCC_PRE") (class "Default")
      (node (ref "R12") (pin "1") (pinfunction "1_1") (pintype "passive"))
      (node (ref "U3") (pin "4") (pinfunction "VIN_4") (pintype "passive"))
    )
    (net (code "96") (name "VCC_SYS") (class "Default")
      (node (ref "C61") (pin "2") (pinfunction "2_2") (pintype "passive"))
      (node (ref "R65") (pin "1") (pinfunction "1_1") (pintype "passive"))
      (node (ref "R66") (pin "1") (pinfunction "1_1") (pintype "passive"))
      (node (ref "R67") (pin "1") (pinfunction "1_1") (pintype "passive"))
      (node (ref "R68") (pin "1") (pinfunction "1_1") (pintype "passive"))
      (node (ref "R69") (pin "1") (pinfunction "1_1") (pintype "passive"))
      (node (ref "R70") (pin "1") (pinfunction "1_1") (pintype "passive"))
      (node (ref "R71") (pin "1") (pinfunction "1_1") (pintype "passive"))
      (node (ref "R72") (pin "1") (pinfunction "1_1") (pintype "passive"))
      (node (ref "R77") (pin "1") (pinfunction "1_1") (pintype "passive"))
      (node (ref "R78") (pin "1") (pinfunction "1_1") (pintype "passive"))
      (node (ref "R9") (pin "2") (pinfunction "2_2") (pintype "passive"))
      (node (ref "U17") (pin "8") (pinfunction "VCC_8") (pintype "passive"))
    )
    (net (code "97") (name "unconnected-(F1D-GAA2{slash}IO67RSB3-Pad2)") (class "Default")
      (node (ref "F1") (pin "2") (pinfunction "GAA2/IO67RSB3_2") (pintype "bidirectional"))
    )
    (net (code "98") (name "unconnected-(F1D-IO66RSB3-Pad3)") (class "Default")
      (node (ref "F1") (pin "3") (pinfunction "IO66RSB3_3") (pintype "bidirectional"))
    )
    (net (code "99") (name "unconnected-(P3-D+-Pad3)") (class "Default")
      (node (ref "P3") (pin "3") (pinfunction "D+_3") (pintype "passive"))
    )
    (net (code "100") (name "unconnected-(P3-D--Pad2)") (class "Default")
      (node (ref "P3") (pin "2") (pinfunction "D-_2") (pintype "passive"))
    )
    (net (code "101") (name "unconnected-(U17-OS-Pad3)") (class "Default")
      (node (ref "U17") (pin "3") (pinfunction "OS_3") (pintype "passive"))
    )
  )
)
